# HM-Relais4-flach-v01-036.net
KiCad netlist of a schematic drawn in EAGLE
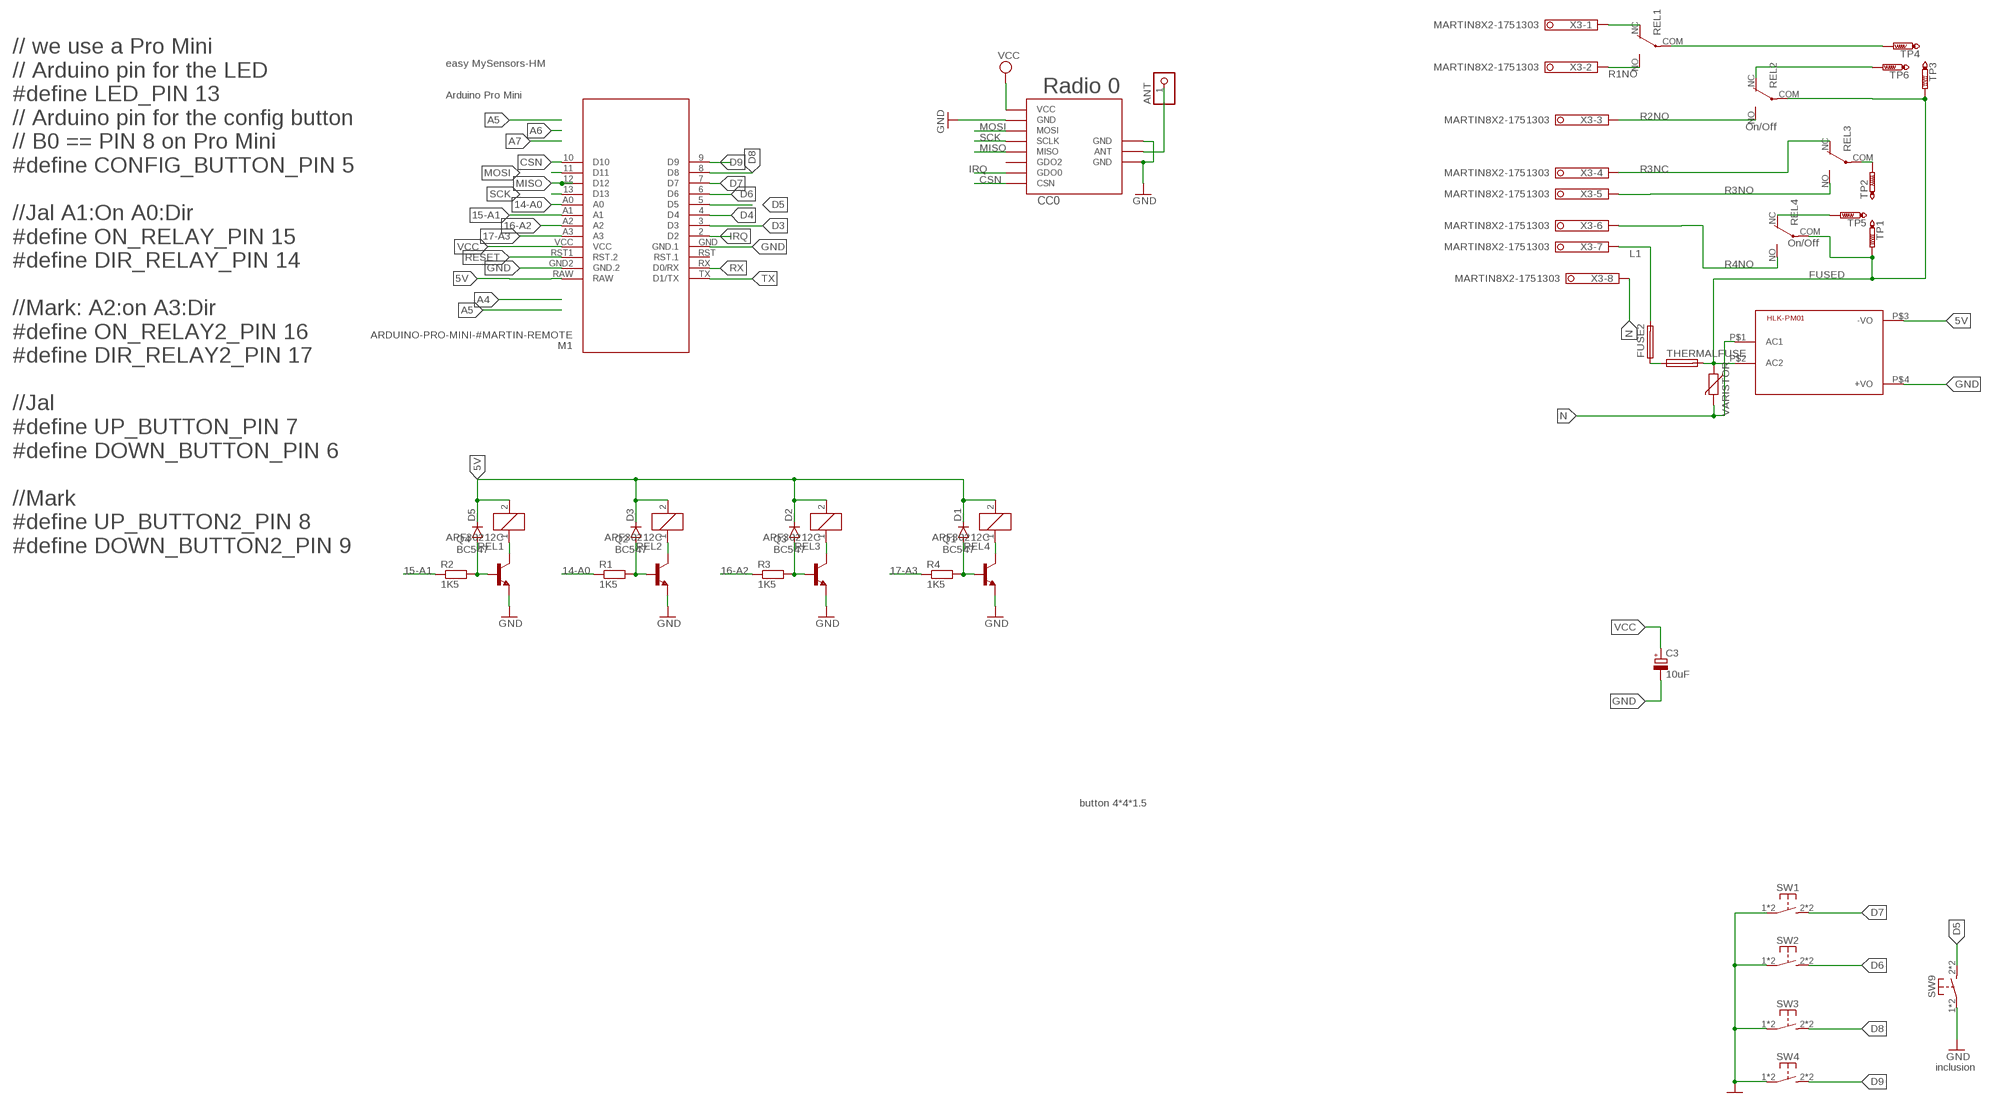
[diagram p0: schematic, sheet 1]

(export (version "E")
  (design (tool "Eeschema 10.0.6"))
  (components
    (comp (ref "ANT")
      (value "PINHD-1X1")
      (footprint "eagle-import:1X01")
      (libsource (lib "eagle-import") (part "PINHD-1X1"))
    )
    (comp (ref "C3")
      (value "10uF")
      (footprint "eagle-import:SMC_C")
      (libsource (lib "eagle-import") (part "CPOL-EUSMCC"))
    )
    (comp (ref "CC0")
      (value "CC1101")
      (footprint "eagle-import:CC1101_MODULE1_SMD")
      (libsource (lib "eagle-import") (part "CC1101_MODULE1SMD"))
    )
    (comp (ref "D1")
      (value "DIODE-D-2.5")
      (footprint "eagle-import:D-2.5")
      (libsource (lib "eagle-import") (part "DIODE-D-2.5"))
    )
    (comp (ref "D2")
      (value "DIODE-D-2.5")
      (footprint "eagle-import:D-2.5")
      (libsource (lib "eagle-import") (part "DIODE-D-2.5"))
    )
    (comp (ref "D3")
      (value "DIODE-D-2.5")
      (footprint "eagle-import:D-2.5")
      (libsource (lib "eagle-import") (part "DIODE-D-2.5"))
    )
    (comp (ref "D5")
      (value "DIODE-D-2.5")
      (footprint "eagle-import:D-2.5")
      (libsource (lib "eagle-import") (part "DIODE-D-2.5"))
    )
    (comp (ref "FUSE2")
      (value "FUSETE5")
      (footprint "eagle-import:TE5")
      (libsource (lib "eagle-import") (part "FUSETE5"))
    )
    (comp (ref "HLK-PM01")
      (value "HKLPM01")
      (footprint "eagle-import:HKLPM01")
      (libsource (lib "eagle-import") (part "HKLPM01"))
    )
    (comp (ref "M1")
      (value "ARDUINO-PRO-MINI-#MARTIN-REMOTE")
      (footprint "eagle-import:ARDUINO-PRO-MINI#NP-MARTIN-REMOTE")
      (libsource (lib "eagle-import") (part "ARDUINO-PRO-MINI-#MARTIN-REMOTE"))
    )
    (comp (ref "Q1")
      (value "BC547")
      (footprint "eagle-import:TO92")
      (libsource (lib "eagle-import") (part "BC547"))
    )
    (comp (ref "Q2")
      (value "BC547")
      (footprint "eagle-import:TO92")
      (libsource (lib "eagle-import") (part "BC547"))
    )
    (comp (ref "Q3")
      (value "BC547")
      (footprint "eagle-import:TO92")
      (libsource (lib "eagle-import") (part "BC547"))
    )
    (comp (ref "Q4")
      (value "BC547")
      (footprint "eagle-import:TO92")
      (libsource (lib "eagle-import") (part "BC547"))
    )
    (comp (ref "R1")
      (value "1K5")
      (footprint "eagle-import:0207_2V")
      (libsource (lib "eagle-import") (part "R-EU_0207/2V"))
    )
    (comp (ref "R2")
      (value "1K5")
      (footprint "eagle-import:0207_2V")
      (libsource (lib "eagle-import") (part "R-EU_0207/2V"))
    )
    (comp (ref "R3")
      (value "1K5")
      (footprint "eagle-import:0207_2V")
      (libsource (lib "eagle-import") (part "R-EU_0207/2V"))
    )
    (comp (ref "R4")
      (value "1K5")
      (footprint "eagle-import:0207_2V")
      (libsource (lib "eagle-import") (part "R-EU_0207/2V"))
    )
    (comp (ref "REL1")
      (value "APF30212C")
      (footprint "eagle-import:APF30212C")
      (libsource (lib "eagle-import") (part "APF30212C"))
    )
    (comp (ref "REL2")
      (value "APF30212C")
      (footprint "eagle-import:APF30212C")
      (libsource (lib "eagle-import") (part "APF30212C"))
    )
    (comp (ref "REL3")
      (value "APF30212C")
      (footprint "eagle-import:APF30212C")
      (libsource (lib "eagle-import") (part "APF30212C"))
    )
    (comp (ref "REL4")
      (value "APF30212C")
      (footprint "eagle-import:APF30212C")
      (libsource (lib "eagle-import") (part "APF30212C"))
    )
    (comp (ref "SW1")
      (value "SW-TACTILE-TL3305")
      (footprint "eagle-import:TL3305")
      (libsource (lib "eagle-import") (part "SW-TACTILE-TL3305"))
    )
    (comp (ref "SW2")
      (value "SW-TACTILE-TL3305")
      (footprint "eagle-import:TL3305")
      (libsource (lib "eagle-import") (part "SW-TACTILE-TL3305"))
    )
    (comp (ref "SW3")
      (value "SW-TACTILE-TL3305")
      (footprint "eagle-import:TL3305")
      (libsource (lib "eagle-import") (part "SW-TACTILE-TL3305"))
    )
    (comp (ref "SW4")
      (value "SW-TACTILE-TL3305")
      (footprint "eagle-import:TL3305")
      (libsource (lib "eagle-import") (part "SW-TACTILE-TL3305"))
    )
    (comp (ref "SW9")
      (value "SW-TACTILE-TL3305")
      (footprint "eagle-import:TL3305")
      (libsource (lib "eagle-import") (part "SW-TACTILE-TL3305"))
    )
    (comp (ref "THERMALFUSE")
      (value "FUSETE5")
      (footprint "eagle-import:TE5")
      (libsource (lib "eagle-import") (part "FUSETE5"))
    )
    (comp (ref "TP1")
      (value "PTR1TP11SQ")
      (footprint "eagle-import:TP11SQ")
      (libsource (lib "eagle-import") (part "PTR1TP11SQ"))
    )
    (comp (ref "TP2")
      (value "PTR1TP11SQ")
      (footprint "eagle-import:TP11SQ")
      (libsource (lib "eagle-import") (part "PTR1TP11SQ"))
    )
    (comp (ref "TP3")
      (value "PTR1TP11SQ")
      (footprint "eagle-import:TP11SQ")
      (libsource (lib "eagle-import") (part "PTR1TP11SQ"))
    )
    (comp (ref "TP4")
      (value "PTR1TP11SQ")
      (footprint "eagle-import:TP11SQ")
      (libsource (lib "eagle-import") (part "PTR1TP11SQ"))
    )
    (comp (ref "TP5")
      (value "PTR1TP11SQ")
      (footprint "eagle-import:TP11SQ")
      (libsource (lib "eagle-import") (part "PTR1TP11SQ"))
    )
    (comp (ref "TP6")
      (value "PTR1TP11SQ")
      (footprint "eagle-import:TP11SQ")
      (libsource (lib "eagle-import") (part "PTR1TP11SQ"))
    )
    (comp (ref "VARISTOR")
      (value "VARISTOR-7,5")
      (footprint "eagle-import:R-7,5")
      (libsource (lib "eagle-import") (part "VARISTOR-7,5"))
    )
    (comp (ref "X3")
      (value "MARTIN8X2-1751303")
      (footprint "eagle-import:1751303")
      (libsource (lib "eagle-import") (part "MARTIN8X2-1751303"))
    )
  )
  (nets
    (net (code "1") (name "/FUSED") (class "Default")
      (node (ref "HLK-PM01") (pin "P$2") (pinfunction "AC2_P$2") (pintype "bidirectional"))
      (node (ref "REL2") (pin "COM") (pinfunction "P_COM") (pintype "passive"))
      (node (ref "REL4") (pin "COM") (pinfunction "P_COM") (pintype "passive"))
      (node (ref "THERMALFUSE") (pin "2") (pinfunction "2_2") (pintype "passive"))
      (node (ref "TP1") (pin "TP") (pinfunction "TP_TP") (pintype "input"))
      (node (ref "TP3") (pin "TP") (pinfunction "TP_TP") (pintype "input"))
      (node (ref "VARISTOR") (pin "1") (pinfunction "1_1") (pintype "passive"))
    )
    (net (code "2") (name "/L1") (class "Default")
      (node (ref "FUSE2") (pin "2") (pinfunction "2_2") (pintype "passive"))
      (node (ref "X3") (pin "15") (pinfunction "K_15") (pintype "passive"))
    )
    (net (code "3") (name "/R1NO") (class "Default")
      (node (ref "REL1") (pin "NO") (pinfunction "S_NO") (pintype "passive"))
      (node (ref "X3") (pin "10") (pinfunction "K_10") (pintype "passive"))
    )
    (net (code "4") (name "/R2NO") (class "Default")
      (node (ref "REL2") (pin "NO") (pinfunction "S_NO") (pintype "passive"))
      (node (ref "X3") (pin "11") (pinfunction "K_11") (pintype "passive"))
    )
    (net (code "5") (name "/R3NC") (class "Default")
      (node (ref "REL3") (pin "NC") (pinfunction "O_NC") (pintype "passive"))
      (node (ref "X3") (pin "12") (pinfunction "K_12") (pintype "passive"))
    )
    (net (code "6") (name "/R3NO") (class "Default")
      (node (ref "REL3") (pin "NO") (pinfunction "S_NO") (pintype "passive"))
      (node (ref "X3") (pin "13") (pinfunction "K_13") (pintype "passive"))
    )
    (net (code "7") (name "/R4NO") (class "Default")
      (node (ref "REL4") (pin "NO") (pinfunction "S_NO") (pintype "passive"))
      (node (ref "X3") (pin "14") (pinfunction "K_14") (pintype "passive"))
    )
    (net (code "8") (name "5V") (class "Default")
      (node (ref "D1") (pin "C") (pinfunction "C_C") (pintype "passive"))
      (node (ref "D2") (pin "C") (pinfunction "C_C") (pintype "passive"))
      (node (ref "D3") (pin "C") (pinfunction "C_C") (pintype "passive"))
      (node (ref "D5") (pin "C") (pinfunction "C_C") (pintype "passive"))
      (node (ref "HLK-PM01") (pin "P$3") (pinfunction "-VO_P$3") (pintype "bidirectional"))
      (node (ref "M1") (pin "RAW") (pinfunction "RAW_RAW") (pintype "power_in"))
      (node (ref "REL1") (pin "2") (pinfunction "2_2") (pintype "passive"))
      (node (ref "REL2") (pin "2") (pinfunction "2_2") (pintype "passive"))
      (node (ref "REL3") (pin "2") (pinfunction "2_2") (pintype "passive"))
      (node (ref "REL4") (pin "2") (pinfunction "2_2") (pintype "passive"))
    )
    (net (code "9") (name "14-A0") (class "Default")
      (node (ref "M1") (pin "A0") (pinfunction "A0_A0") (pintype "bidirectional"))
      (node (ref "R1") (pin "1") (pinfunction "1_1") (pintype "passive"))
    )
    (net (code "10") (name "15-A1") (class "Default")
      (node (ref "M1") (pin "A1") (pinfunction "A1_A1") (pintype "bidirectional"))
      (node (ref "R2") (pin "1") (pinfunction "1_1") (pintype "passive"))
    )
    (net (code "11") (name "16-A2") (class "Default")
      (node (ref "M1") (pin "A2") (pinfunction "A2_A2") (pintype "bidirectional"))
      (node (ref "R3") (pin "1") (pinfunction "1_1") (pintype "passive"))
    )
    (net (code "12") (name "17-A3") (class "Default")
      (node (ref "M1") (pin "A3") (pinfunction "A3_A3") (pintype "bidirectional"))
      (node (ref "R4") (pin "1") (pinfunction "1_1") (pintype "passive"))
    )
    (net (code "17") (name "CSN") (class "Default")
      (node (ref "CC0") (pin "CSN") (pinfunction "CSN_CSN") (pintype "bidirectional"))
      (node (ref "M1") (pin "10") (pinfunction "D10_10") (pintype "bidirectional"))
    )
    (net (code "18") (name "D3") (class "Default")
      (node (ref "M1") (pin "3") (pinfunction "D3_3") (pintype "bidirectional"))
    )
    (net (code "19") (name "D4") (class "Default")
      (node (ref "M1") (pin "4") (pinfunction "D4_4") (pintype "bidirectional"))
    )
    (net (code "20") (name "D5") (class "Default")
      (node (ref "M1") (pin "5") (pinfunction "D5_5") (pintype "bidirectional"))
      (node (ref "SW9") (pin "2") (pinfunction "S1_2") (pintype "passive"))
      (node (ref "SW9") (pin "3") (pinfunction "S1_3") (pintype "passive"))
    )
    (net (code "21") (name "D6") (class "Default")
      (node (ref "M1") (pin "6") (pinfunction "D6_6") (pintype "bidirectional"))
      (node (ref "SW2") (pin "2") (pinfunction "S1_2") (pintype "passive"))
      (node (ref "SW2") (pin "3") (pinfunction "S1_3") (pintype "passive"))
    )
    (net (code "22") (name "D7") (class "Default")
      (node (ref "M1") (pin "7") (pinfunction "D7_7") (pintype "bidirectional"))
      (node (ref "SW1") (pin "2") (pinfunction "S1_2") (pintype "passive"))
      (node (ref "SW1") (pin "3") (pinfunction "S1_3") (pintype "passive"))
    )
    (net (code "23") (name "D8") (class "Default")
      (node (ref "M1") (pin "8") (pinfunction "D8_8") (pintype "bidirectional"))
      (node (ref "SW3") (pin "2") (pinfunction "S1_2") (pintype "passive"))
      (node (ref "SW3") (pin "3") (pinfunction "S1_3") (pintype "passive"))
    )
    (net (code "24") (name "D9") (class "Default")
      (node (ref "M1") (pin "9") (pinfunction "D9_9") (pintype "bidirectional"))
      (node (ref "SW4") (pin "2") (pinfunction "S1_2") (pintype "passive"))
      (node (ref "SW4") (pin "3") (pinfunction "S1_3") (pintype "passive"))
    )
    (net (code "25") (name "GND") (class "Default")
      (node (ref "C3") (pin "-") (pinfunction "-_-") (pintype "passive"))
      (node (ref "CC0") (pin "GND@0") (pinfunction "GND_GND@0") (pintype "power_in"))
      (node (ref "CC0") (pin "GND@1") (pinfunction "GND_GND@1") (pintype "power_in"))
      (node (ref "CC0") (pin "GND@2") (pinfunction "GND_GND@2") (pintype "power_in"))
      (node (ref "HLK-PM01") (pin "P$4") (pinfunction "+VO_P$4") (pintype "bidirectional"))
      (node (ref "M1") (pin "GND") (pinfunction "GND.1_GND") (pintype "power_in"))
      (node (ref "M1") (pin "GND2") (pinfunction "GND.2_GND2") (pintype "power_in"))
      (node (ref "Q1") (pin "1") (pinfunction "E_1") (pintype "passive"))
      (node (ref "Q2") (pin "1") (pinfunction "E_1") (pintype "passive"))
      (node (ref "Q3") (pin "1") (pinfunction "E_1") (pintype "passive"))
      (node (ref "Q4") (pin "1") (pinfunction "E_1") (pintype "passive"))
      (node (ref "SW1") (pin "1") (pinfunction "P1_1") (pintype "passive"))
      (node (ref "SW1") (pin "4") (pinfunction "P1_4") (pintype "passive"))
      (node (ref "SW2") (pin "1") (pinfunction "P1_1") (pintype "passive"))
      (node (ref "SW2") (pin "4") (pinfunction "P1_4") (pintype "passive"))
      (node (ref "SW3") (pin "1") (pinfunction "P1_1") (pintype "passive"))
      (node (ref "SW3") (pin "4") (pinfunction "P1_4") (pintype "passive"))
      (node (ref "SW4") (pin "1") (pinfunction "P1_1") (pintype "passive"))
      (node (ref "SW4") (pin "4") (pinfunction "P1_4") (pintype "passive"))
      (node (ref "SW9") (pin "1") (pinfunction "P1_1") (pintype "passive"))
      (node (ref "SW9") (pin "4") (pinfunction "P1_4") (pintype "passive"))
    )
    (net (code "26") (name "IRQ") (class "Default")
      (node (ref "CC0") (pin "GDO0") (pinfunction "GDO0_GDO0") (pintype "bidirectional"))
      (node (ref "M1") (pin "2") (pinfunction "D2_2") (pintype "bidirectional"))
    )
    (net (code "27") (name "MISO") (class "Default")
      (node (ref "CC0") (pin "MISO") (pinfunction "MISO_MISO") (pintype "bidirectional"))
      (node (ref "M1") (pin "12") (pinfunction "D12_12") (pintype "bidirectional"))
    )
    (net (code "28") (name "MOSI") (class "Default")
      (node (ref "CC0") (pin "MOSI") (pinfunction "MOSI_MOSI") (pintype "bidirectional"))
      (node (ref "M1") (pin "11") (pinfunction "D11_11") (pintype "bidirectional"))
    )
    (net (code "29") (name "N") (class "Default")
      (node (ref "HLK-PM01") (pin "P$1") (pinfunction "AC1_P$1") (pintype "bidirectional"))
      (node (ref "VARISTOR") (pin "2") (pinfunction "2_2") (pintype "passive"))
      (node (ref "X3") (pin "16") (pinfunction "K_16") (pintype "passive"))
    )
    (net (code "30") (name "Net-(ANT-Pad1)") (class "Default")
      (node (ref "ANT") (pin "1") (pinfunction "1_1") (pintype "passive"))
      (node (ref "CC0") (pin "ANT") (pinfunction "ANT_ANT") (pintype "output"))
    )
    (net (code "31") (name "Net-(FUSE2-Pad1)") (class "Default")
      (node (ref "FUSE2") (pin "1") (pinfunction "1_1") (pintype "passive"))
      (node (ref "THERMALFUSE") (pin "1") (pinfunction "1_1") (pintype "passive"))
    )
    (net (code "32") (name "Net-(Q1-B)") (class "Default")
      (node (ref "D1") (pin "A") (pinfunction "A_A") (pintype "passive"))
      (node (ref "Q1") (pin "2") (pinfunction "B_2") (pintype "passive"))
      (node (ref "R4") (pin "2") (pinfunction "2_2") (pintype "passive"))
    )
    (net (code "33") (name "Net-(Q1-C)") (class "Default")
      (node (ref "Q1") (pin "3") (pinfunction "C_3") (pintype "passive"))
      (node (ref "REL4") (pin "1") (pinfunction "1_1") (pintype "passive"))
    )
    (net (code "34") (name "Net-(Q2-B)") (class "Default")
      (node (ref "D3") (pin "A") (pinfunction "A_A") (pintype "passive"))
      (node (ref "Q2") (pin "2") (pinfunction "B_2") (pintype "passive"))
      (node (ref "R1") (pin "2") (pinfunction "2_2") (pintype "passive"))
    )
    (net (code "35") (name "Net-(Q2-C)") (class "Default")
      (node (ref "Q2") (pin "3") (pinfunction "C_3") (pintype "passive"))
      (node (ref "REL2") (pin "1") (pinfunction "1_1") (pintype "passive"))
    )
    (net (code "36") (name "Net-(Q3-B)") (class "Default")
      (node (ref "D2") (pin "A") (pinfunction "A_A") (pintype "passive"))
      (node (ref "Q3") (pin "2") (pinfunction "B_2") (pintype "passive"))
      (node (ref "R3") (pin "2") (pinfunction "2_2") (pintype "passive"))
    )
    (net (code "37") (name "Net-(Q3-C)") (class "Default")
      (node (ref "Q3") (pin "3") (pinfunction "C_3") (pintype "passive"))
      (node (ref "REL3") (pin "1") (pinfunction "1_1") (pintype "passive"))
    )
    (net (code "38") (name "Net-(Q4-B)") (class "Default")
      (node (ref "D5") (pin "A") (pinfunction "A_A") (pintype "passive"))
      (node (ref "Q4") (pin "2") (pinfunction "B_2") (pintype "passive"))
      (node (ref "R2") (pin "2") (pinfunction "2_2") (pintype "passive"))
    )
    (net (code "39") (name "Net-(Q4-C)") (class "Default")
      (node (ref "Q4") (pin "3") (pinfunction "C_3") (pintype "passive"))
      (node (ref "REL1") (pin "1") (pinfunction "1_1") (pintype "passive"))
    )
    (net (code "40") (name "Net-(REL1B-O)") (class "Default")
      (node (ref "REL1") (pin "NC") (pinfunction "O_NC") (pintype "passive"))
      (node (ref "X3") (pin "9") (pinfunction "K_9") (pintype "passive"))
    )
    (net (code "41") (name "Net-(REL1B-P)") (class "Default")
      (node (ref "REL1") (pin "COM") (pinfunction "P_COM") (pintype "passive"))
      (node (ref "TP4") (pin "TP") (pinfunction "TP_TP") (pintype "input"))
    )
    (net (code "42") (name "Net-(REL2B-O)") (class "Default")
      (node (ref "REL2") (pin "NC") (pinfunction "O_NC") (pintype "passive"))
      (node (ref "TP6") (pin "TP") (pinfunction "TP_TP") (pintype "input"))
    )
    (net (code "43") (name "Net-(REL3B-P)") (class "Default")
      (node (ref "REL3") (pin "COM") (pinfunction "P_COM") (pintype "passive"))
      (node (ref "TP2") (pin "TP") (pinfunction "TP_TP") (pintype "input"))
    )
    (net (code "44") (name "Net-(REL4B-O)") (class "Default")
      (node (ref "REL4") (pin "NC") (pinfunction "O_NC") (pintype "passive"))
      (node (ref "TP5") (pin "TP") (pinfunction "TP_TP") (pintype "input"))
    )
    (net (code "45") (name "RESET") (class "Default")
      (node (ref "M1") (pin "RST1") (pinfunction "RST.2_RST1") (pintype "bidirectional"))
    )
    (net (code "46") (name "RX") (class "Default")
      (node (ref "M1") (pin "RX") (pinfunction "D0/RX_RX") (pintype "bidirectional"))
    )
    (net (code "47") (name "SCK") (class "Default")
      (node (ref "CC0") (pin "SCLK") (pinfunction "SCLK_SCLK") (pintype "bidirectional"))
      (node (ref "M1") (pin "13") (pinfunction "D13_13") (pintype "bidirectional"))
    )
    (net (code "48") (name "TX") (class "Default")
      (node (ref "M1") (pin "TX") (pinfunction "D1/TX_TX") (pintype "bidirectional"))
    )
    (net (code "49") (name "VCC") (class "Default")
      (node (ref "C3") (pin "+") (pinfunction "+_+") (pintype "passive"))
      (node (ref "CC0") (pin "VCC") (pinfunction "VCC_VCC") (pintype "power_in"))
      (node (ref "M1") (pin "VCC") (pinfunction "VCC_VCC") (pintype "power_in"))
    )
    (net (code "50") (name "unconnected-(CC0-PadGDO2)") (class "Default")
      (node (ref "CC0") (pin "GDO2") (pinfunction "GDO2_GDO2") (pintype "bidirectional"))
    )
    (net (code "51") (name "unconnected-(M1-RST.1-PadRST)") (class "Default")
      (node (ref "M1") (pin "RST") (pinfunction "RST.1_RST") (pintype "bidirectional"))
    )
  )
)
